# MCU.net
KiCad netlist of a schematic drawn in Altium Designer
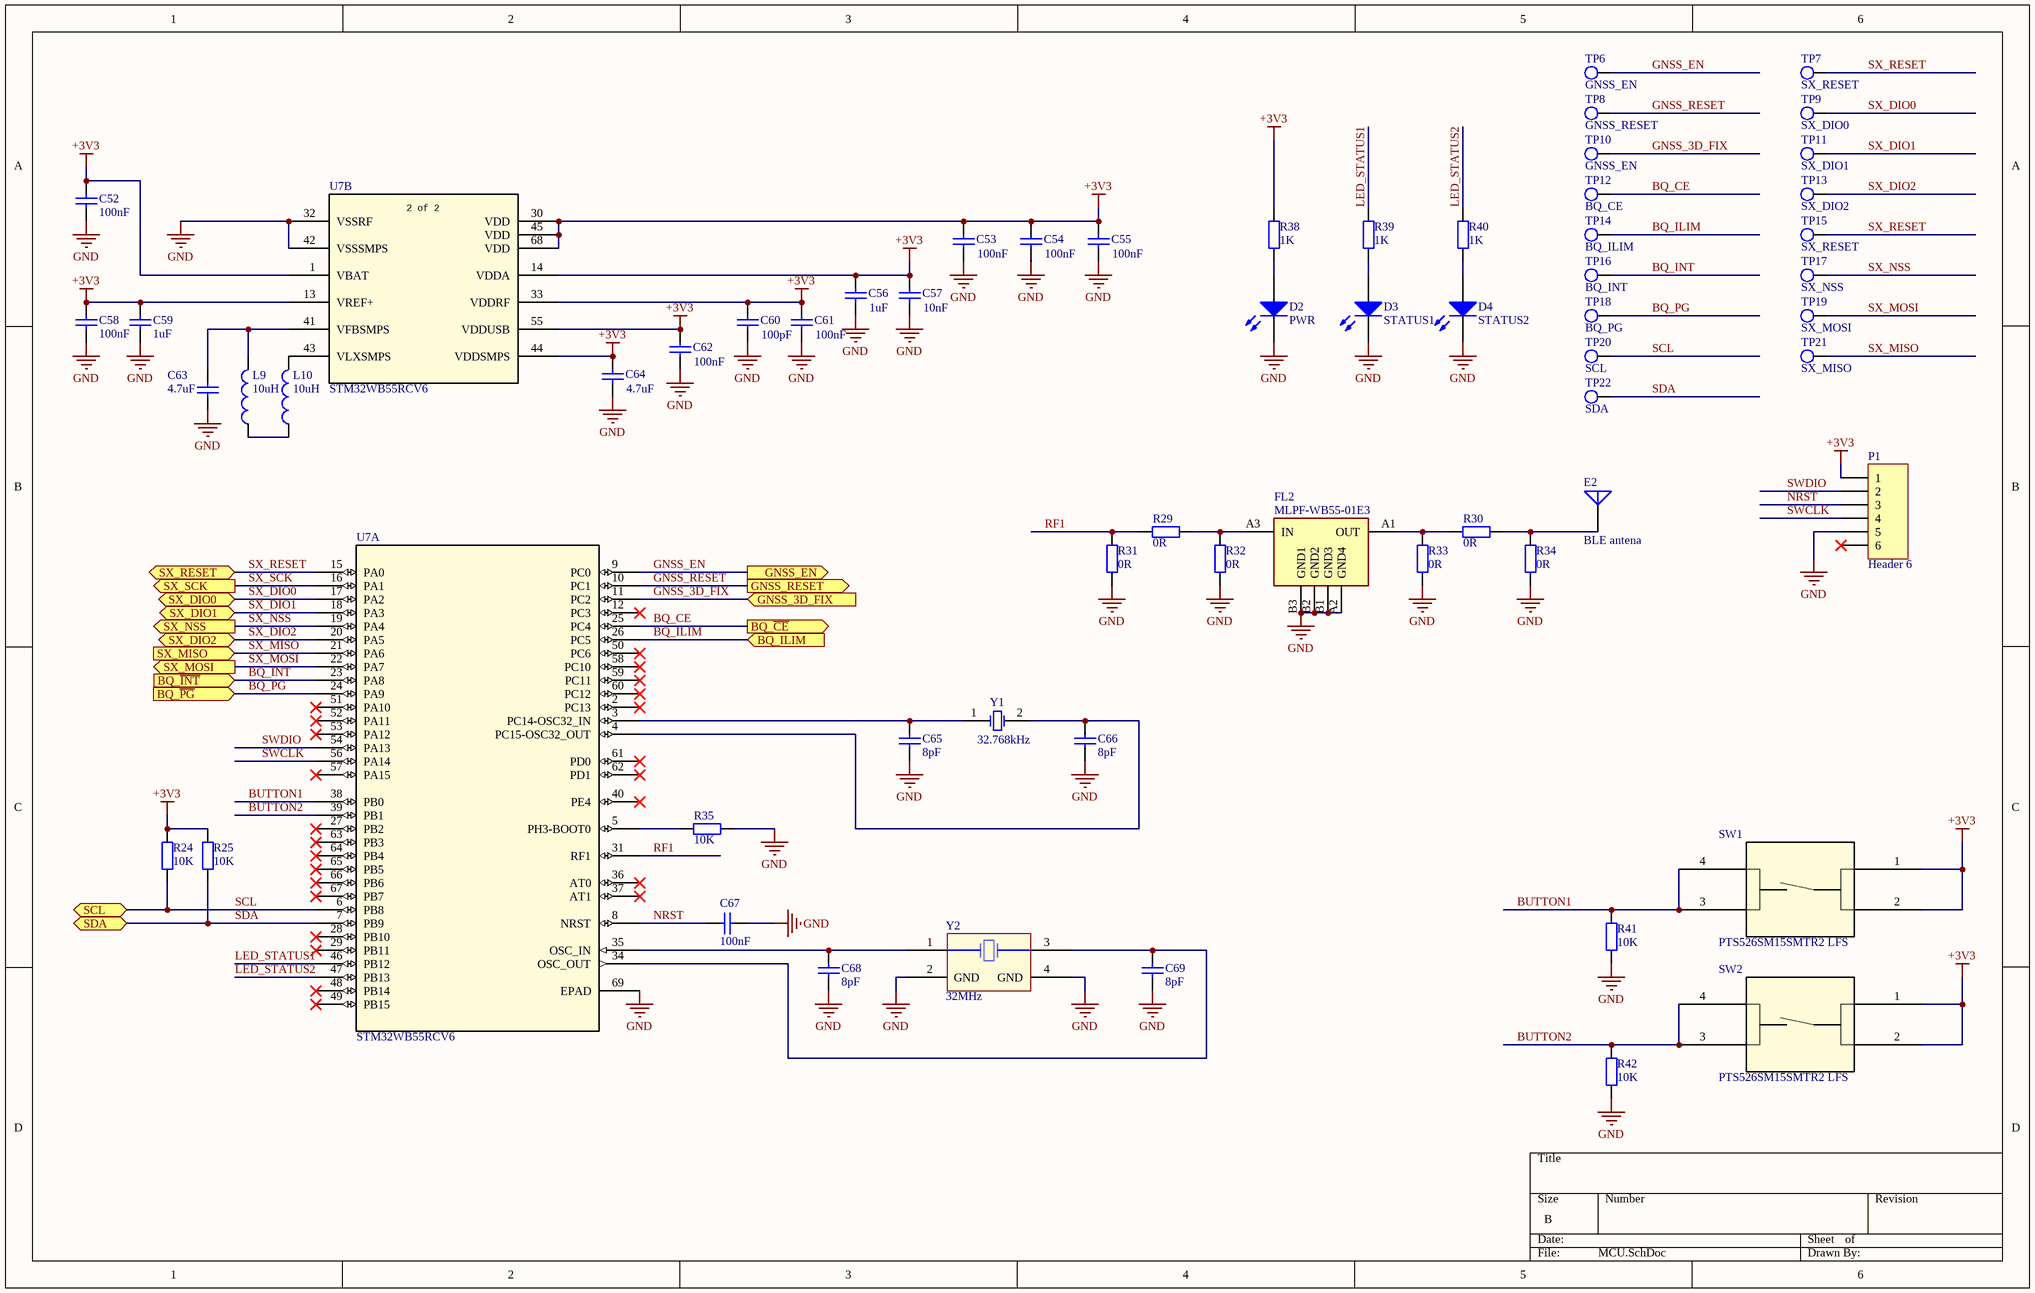
[diagram p0: MCU.SchDoc]

(export (version "E")
  (design (tool "Eeschema 10.0.6"))
  (components
    (comp (ref "C52")
      (value "100nF")
      (footprint "0402")
      (description "Capacitor")
      (fields (field (name "PUBLISHER") "Altium Limited"))
      (libsource (lib "Miscellaneous Devices") (part "Cap"))
    )
    (comp (ref "C53")
      (value "100nF")
      (footprint "0402")
      (description "Capacitor")
      (fields (field (name "PUBLISHER") "Altium Limited"))
      (libsource (lib "Miscellaneous Devices") (part "Cap"))
    )
    (comp (ref "C54")
      (value "100nF")
      (footprint "0402")
      (description "Capacitor")
      (fields (field (name "PUBLISHER") "Altium Limited"))
      (libsource (lib "Miscellaneous Devices") (part "Cap"))
    )
    (comp (ref "C55")
      (value "100nF")
      (footprint "0402")
      (description "Capacitor")
      (fields (field (name "PUBLISHER") "Altium Limited"))
      (libsource (lib "Miscellaneous Devices") (part "Cap"))
    )
    (comp (ref "C56")
      (value "1uF")
      (footprint "0402")
      (description "Capacitor")
      (fields (field (name "PUBLISHER") "Altium Limited"))
      (libsource (lib "Miscellaneous Devices") (part "Cap"))
    )
    (comp (ref "C57")
      (value "10nF")
      (footprint "0402")
      (description "Capacitor")
      (fields (field (name "PUBLISHER") "Altium Limited"))
      (libsource (lib "Miscellaneous Devices") (part "Cap"))
    )
    (comp (ref "C58")
      (value "100nF")
      (footprint "0402")
      (description "Capacitor")
      (fields (field (name "PUBLISHER") "Altium Limited"))
      (libsource (lib "Miscellaneous Devices") (part "Cap"))
    )
    (comp (ref "C59")
      (value "1uF")
      (footprint "0402")
      (description "Capacitor")
      (fields (field (name "PUBLISHER") "Altium Limited"))
      (libsource (lib "Miscellaneous Devices") (part "Cap"))
    )
    (comp (ref "C60")
      (value "100pF")
      (footprint "0402")
      (description "Capacitor")
      (fields (field (name "PUBLISHER") "Altium Limited"))
      (libsource (lib "Miscellaneous Devices") (part "Cap"))
    )
    (comp (ref "C61")
      (value "100nF")
      (footprint "0402")
      (description "Capacitor")
      (fields (field (name "PUBLISHER") "Altium Limited"))
      (libsource (lib "Miscellaneous Devices") (part "Cap"))
    )
    (comp (ref "C62")
      (value "100nF")
      (footprint "0402")
      (description "Capacitor")
      (fields (field (name "PUBLISHER") "Altium Limited"))
      (libsource (lib "Miscellaneous Devices") (part "Cap"))
    )
    (comp (ref "C63")
      (value "4.7uF")
      (footprint "0402")
      (description "Capacitor")
      (fields (field (name "PUBLISHER") "Altium Limited"))
      (libsource (lib "Miscellaneous Devices") (part "Cap"))
    )
    (comp (ref "C64")
      (value "4.7uF")
      (footprint "0402")
      (description "Capacitor")
      (fields (field (name "PUBLISHER") "Altium Limited"))
      (libsource (lib "Miscellaneous Devices") (part "Cap"))
    )
    (comp (ref "C65")
      (value "8pF")
      (footprint "0402")
      (description "Capacitor")
      (fields (field (name "PUBLISHER") "Altium Limited"))
      (libsource (lib "Miscellaneous Devices") (part "Cap"))
    )
    (comp (ref "C66")
      (value "8pF")
      (footprint "0402")
      (description "Capacitor")
      (fields (field (name "PUBLISHER") "Altium Limited"))
      (libsource (lib "Miscellaneous Devices") (part "Cap"))
    )
    (comp (ref "C67")
      (value "100nF")
      (footprint "0402")
      (description "Capacitor")
      (fields (field (name "PUBLISHER") "Altium Limited"))
      (libsource (lib "Miscellaneous Devices") (part "Cap"))
    )
    (comp (ref "C68")
      (value "8pF")
      (footprint "0402")
      (description "Capacitor")
      (fields (field (name "PUBLISHER") "Altium Limited"))
      (libsource (lib "Miscellaneous Devices") (part "Cap"))
    )
    (comp (ref "C69")
      (value "8pF")
      (footprint "0402")
      (description "Capacitor")
      (fields (field (name "PUBLISHER") "Altium Limited"))
      (libsource (lib "Miscellaneous Devices") (part "Cap"))
    )
    (comp (ref "D2")
      (value "PWR")
      (description "SML-D12P8WT86")
      (libsource (lib "Simulation Generic Components") (part "LED"))
    )
    (comp (ref "D3")
      (value "STATUS1")
      (description "SML-D12P8WT86")
      (libsource (lib "Simulation Generic Components") (part "LED"))
    )
    (comp (ref "D4")
      (value "STATUS2")
      (description "SML-D12P8WT86")
      (libsource (lib "Simulation Generic Components") (part "LED"))
    )
    (comp (ref "E2")
      (value "BLE antena")
      (footprint "204286-0001_MOL")
      (description "Generic Antenna")
      (fields (field (name "PUBLISHER") "Altium Limited"))
      (libsource (lib "Miscellaneous Devices") (part "Antenna"))
    )
    (comp (ref "FL2")
      (value "MLPF-WB55-01E3")
      (footprint "MLPF-WB55-01E3")
      (fields (field (name "MOUSER PART NUMBER") "511-MLPF-WB55-01E3"))
      (libsource (lib "Schematic_library") (part "MLPF-WB55-01E3"))
    )
    (comp (ref "L9")
      (value "10uH")
      (footprint "0402-A")
      (description "Inductor")
      (fields (field (name "PUBLISHER") "Altium Limited"))
      (libsource (lib "Miscellaneous Devices") (part "Inductor"))
    )
    (comp (ref "L10")
      (value "10uH")
      (footprint "0402-A")
      (description "Inductor")
      (fields (field (name "PUBLISHER") "Altium Limited"))
      (libsource (lib "Miscellaneous Devices") (part "Inductor"))
    )
    (comp (ref "P1")
      (value "Header 6")
      (footprint "TAG_TC2030-IDC-NL")
      (description "Header, 6-Pin")
      (fields (field (name "PUBLISHER") "Altium Limited"))
      (libsource (lib "Miscellaneous Connectors") (part "Header 6"))
    )
    (comp (ref "R24")
      (value "10K")
      (footprint "SMD-0402-RES")
      (description "Resistor")
      (fields (field (name "PUBLISHER") "Altium Limited"))
      (libsource (lib "Miscellaneous Devices") (part "Res2"))
    )
    (comp (ref "R25")
      (value "10K")
      (footprint "SMD-0402-RES")
      (description "Resistor")
      (fields (field (name "PUBLISHER") "Altium Limited"))
      (libsource (lib "Miscellaneous Devices") (part "Res2"))
    )
    (comp (ref "R29")
      (value "0R")
      (footprint "SMD-0402-RES")
      (description "Resistor")
      (fields (field (name "PUBLISHER") "Altium Limited"))
      (libsource (lib "") (part "Res2_2"))
    )
    (comp (ref "R30")
      (value "0R")
      (footprint "SMD-0402-RES")
      (description "Resistor")
      (fields (field (name "PUBLISHER") "Altium Limited"))
      (libsource (lib "") (part "Res2_2"))
    )
    (comp (ref "R31")
      (value "0R")
      (footprint "SMD-0402-RES")
      (description "Resistor")
      (fields (field (name "PUBLISHER") "Altium Limited"))
      (libsource (lib "Miscellaneous Devices") (part "Res2"))
    )
    (comp (ref "R32")
      (value "0R")
      (footprint "SMD-0402-RES")
      (description "Resistor")
      (fields (field (name "PUBLISHER") "Altium Limited"))
      (libsource (lib "Miscellaneous Devices") (part "Res2"))
    )
    (comp (ref "R33")
      (value "0R")
      (footprint "SMD-0402-RES")
      (description "Resistor")
      (fields (field (name "PUBLISHER") "Altium Limited"))
      (libsource (lib "Miscellaneous Devices") (part "Res2"))
    )
    (comp (ref "R34")
      (value "0R")
      (footprint "SMD-0402-RES")
      (description "Resistor")
      (fields (field (name "PUBLISHER") "Altium Limited"))
      (libsource (lib "Miscellaneous Devices") (part "Res2"))
    )
    (comp (ref "R35")
      (value "10K")
      (footprint "SMD-0402-RES")
      (description "Resistor")
      (fields (field (name "PUBLISHER") "Altium Limited"))
      (libsource (lib "") (part "Res2_3"))
    )
    (comp (ref "R38")
      (value "1K")
      (footprint "SMD-0402-RES")
      (description "Resistor")
      (fields (field (name "PUBLISHER") "Altium Limited"))
      (libsource (lib "") (part "Res2_1"))
    )
    (comp (ref "R39")
      (value "1K")
      (footprint "SMD-0402-RES")
      (description "Resistor")
      (fields (field (name "PUBLISHER") "Altium Limited"))
      (libsource (lib "") (part "Res2_1"))
    )
    (comp (ref "R40")
      (value "1K")
      (footprint "SMD-0402-RES")
      (description "Resistor")
      (fields (field (name "PUBLISHER") "Altium Limited"))
      (libsource (lib "") (part "Res2_1"))
    )
    (comp (ref "R41")
      (value "10K")
      (footprint "SMD-0402-RES")
      (description "Resistor")
      (fields (field (name "PUBLISHER") "Altium Limited"))
      (libsource (lib "") (part "Res2_1"))
    )
    (comp (ref "R42")
      (value "10K")
      (footprint "SMD-0402-RES")
      (description "Resistor")
      (fields (field (name "PUBLISHER") "Altium Limited"))
      (libsource (lib "") (part "Res2_1"))
    )
    (comp (ref "SW1")
      (value "PTS526SM15SMTR2 LFS")
      (footprint "PTS526SM15SMTR2 LFS")
      (fields
        (field (name "MANUFACTURER_PART_NUMBER") "PTS526 SM15 SMTR2 LFS")
        (field (name "COPYRIGHT") "Copyright (C) 2026 Ultra Librarian. All rights reserved.")
      )
      (libsource (lib "Schematic_library") (part "PTS526SM15SMTR2 LFS"))
    )
    (comp (ref "SW2")
      (value "PTS526SM15SMTR2 LFS")
      (footprint "PTS526SM15SMTR2 LFS")
      (fields
        (field (name "MANUFACTURER_PART_NUMBER") "PTS526 SM15 SMTR2 LFS")
        (field (name "COPYRIGHT") "Copyright (C) 2026 Ultra Librarian. All rights reserved.")
      )
      (libsource (lib "Schematic_library") (part "PTS526SM15SMTR2 LFS"))
    )
    (comp (ref "TP6")
      (value "GNSS_EN")
      (footprint "testpoint 1 mm")
      (libsource (lib "Schematic_library") (part "testpoint"))
    )
    (comp (ref "TP7")
      (value "SX_RESET")
      (footprint "testpoint 1 mm")
      (libsource (lib "Schematic_library") (part "testpoint"))
    )
    (comp (ref "TP8")
      (value "GNSS_RESET")
      (footprint "testpoint 1 mm")
      (libsource (lib "Schematic_library") (part "testpoint"))
    )
    (comp (ref "TP9")
      (value "SX_DIO0")
      (footprint "testpoint 1 mm")
      (libsource (lib "Schematic_library") (part "testpoint"))
    )
    (comp (ref "TP10")
      (value "GNSS_EN")
      (footprint "testpoint 1 mm")
      (libsource (lib "Schematic_library") (part "testpoint"))
    )
    (comp (ref "TP11")
      (value "SX_DIO1")
      (footprint "testpoint 1 mm")
      (libsource (lib "Schematic_library") (part "testpoint"))
    )
    (comp (ref "TP12")
      (value "BQ_CE")
      (footprint "testpoint 1 mm")
      (libsource (lib "Schematic_library") (part "testpoint"))
    )
    (comp (ref "TP13")
      (value "SX_DIO2")
      (footprint "testpoint 1 mm")
      (libsource (lib "Schematic_library") (part "testpoint"))
    )
    (comp (ref "TP14")
      (value "BQ_ILIM")
      (footprint "testpoint 1 mm")
      (libsource (lib "Schematic_library") (part "testpoint"))
    )
    (comp (ref "TP15")
      (value "SX_RESET")
      (footprint "testpoint 1 mm")
      (libsource (lib "Schematic_library") (part "testpoint"))
    )
    (comp (ref "TP16")
      (value "BQ_INT")
      (footprint "testpoint 1 mm")
      (libsource (lib "Schematic_library") (part "testpoint"))
    )
    (comp (ref "TP17")
      (value "SX_NSS")
      (footprint "testpoint 1 mm")
      (libsource (lib "Schematic_library") (part "testpoint"))
    )
    (comp (ref "TP18")
      (value "BQ_PG")
      (footprint "testpoint 1 mm")
      (libsource (lib "Schematic_library") (part "testpoint"))
    )
    (comp (ref "TP19")
      (value "SX_MOSI")
      (footprint "testpoint 1 mm")
      (libsource (lib "Schematic_library") (part "testpoint"))
    )
    (comp (ref "TP20")
      (value "SCL")
      (footprint "testpoint 1 mm")
      (libsource (lib "Schematic_library") (part "testpoint"))
    )
    (comp (ref "TP21")
      (value "SX_MISO")
      (footprint "testpoint 1 mm")
      (libsource (lib "Schematic_library") (part "testpoint"))
    )
    (comp (ref "TP22")
      (value "SDA")
      (footprint "testpoint 1 mm")
      (libsource (lib "Schematic_library") (part "testpoint"))
    )
    (comp (ref "U7")
      (value "STM32WB55RCV6")
      (footprint "STM32WB55RCV6")
      (fields (field (name "COPYRIGHT") "Copyright (C) 2025 Ultra Librarian. All rights reserved."))
      (libsource (lib "Schematic_library") (part "STM32WB55RCV6"))
    )
    (comp (ref "Y1")
      (value "32.768kHz")
      (footprint "CM8V-T1A-32.768kHz-7pF-20PPM-TA-QC")
      (description "Crystal Oscillator\r\nCM8V-T1A-32.768kHz-7pF-20PPM-TA-QC")
      (fields (field (name "PUBLISHER") "Altium Limited"))
      (libsource (lib "Miscellaneous Devices") (part "XTAL"))
    )
    (comp (ref "Y2")
      (value "32MHz")
      (footprint "ECS-TXO-20CSMV-320-EY-TR")
      (libsource (lib "Schematic_library") (part "Xtal 4 pin"))
    )
  )
  (nets
    (net (code "1") (name "+3V3") (class "Default")
      (node (ref "C52") (pin "2") (pinfunction "2_2") (pintype "passive"))
      (node (ref "C53") (pin "2") (pinfunction "2_2") (pintype "passive"))
      (node (ref "C54") (pin "2") (pinfunction "2_2") (pintype "passive"))
      (node (ref "C55") (pin "2") (pinfunction "2_2") (pintype "passive"))
      (node (ref "C56") (pin "2") (pinfunction "2_2") (pintype "passive"))
      (node (ref "C57") (pin "2") (pinfunction "2_2") (pintype "passive"))
      (node (ref "C58") (pin "2") (pinfunction "2_2") (pintype "passive"))
      (node (ref "C59") (pin "2") (pinfunction "2_2") (pintype "passive"))
      (node (ref "C60") (pin "2") (pinfunction "2_2") (pintype "passive"))
      (node (ref "C61") (pin "2") (pinfunction "2_2") (pintype "passive"))
      (node (ref "C62") (pin "2") (pinfunction "2_2") (pintype "passive"))
      (node (ref "C64") (pin "2") (pinfunction "2_2") (pintype "passive"))
      (node (ref "P1") (pin "1") (pinfunction "1_1") (pintype "passive"))
      (node (ref "R24") (pin "2") (pinfunction "2_2") (pintype "passive"))
      (node (ref "R25") (pin "2") (pinfunction "2_2") (pintype "passive"))
      (node (ref "R38") (pin "1") (pinfunction "1_1") (pintype "passive"))
      (node (ref "SW1") (pin "1") (pinfunction "1_1") (pintype "passive"))
      (node (ref "SW1") (pin "2") (pinfunction "2_2") (pintype "passive"))
      (node (ref "SW2") (pin "1") (pinfunction "1_1") (pintype "passive"))
      (node (ref "SW2") (pin "2") (pinfunction "2_2") (pintype "passive"))
      (node (ref "U7") (pin "1") (pinfunction "VBAT_1") (pintype "power_in"))
      (node (ref "U7") (pin "13") (pinfunction "VREF+_13") (pintype "power_in"))
      (node (ref "U7") (pin "14") (pinfunction "VDDA_14") (pintype "power_in"))
      (node (ref "U7") (pin "30") (pinfunction "VDD_30") (pintype "power_in"))
      (node (ref "U7") (pin "33") (pinfunction "VDDRF_33") (pintype "power_in"))
      (node (ref "U7") (pin "44") (pinfunction "VDDSMPS_44") (pintype "power_in"))
      (node (ref "U7") (pin "45") (pinfunction "VDD_45") (pintype "power_in"))
      (node (ref "U7") (pin "55") (pinfunction "VDDUSB_55") (pintype "power_in"))
      (node (ref "U7") (pin "68") (pinfunction "VDD_68") (pintype "power_in"))
    )
    (net (code "2") (name "/BQ_CE") (class "Default")
      (node (ref "TP12") (pin "1") (pinfunction "1_1") (pintype "passive"))
      (node (ref "U7") (pin "25") (pinfunction "PC4_25") (pintype "bidirectional"))
    )
    (net (code "3") (name "/BQ_ILIM") (class "Default")
      (node (ref "TP14") (pin "1") (pinfunction "1_1") (pintype "passive"))
      (node (ref "U7") (pin "26") (pinfunction "PC5_26") (pintype "bidirectional"))
    )
    (net (code "4") (name "/BQ_INT") (class "Default")
      (node (ref "TP16") (pin "1") (pinfunction "1_1") (pintype "passive"))
      (node (ref "U7") (pin "23") (pinfunction "PA8_23") (pintype "bidirectional"))
    )
    (net (code "5") (name "/BQ_PG") (class "Default")
      (node (ref "TP18") (pin "1") (pinfunction "1_1") (pintype "passive"))
      (node (ref "U7") (pin "24") (pinfunction "PA9_24") (pintype "bidirectional"))
    )
    (net (code "6") (name "/BUTTON1") (class "Default")
      (node (ref "R41") (pin "1") (pinfunction "1_1") (pintype "passive"))
      (node (ref "SW1") (pin "3") (pinfunction "3_3") (pintype "passive"))
      (node (ref "SW1") (pin "4") (pinfunction "4_4") (pintype "passive"))
      (node (ref "U7") (pin "38") (pinfunction "PB0_38") (pintype "bidirectional"))
    )
    (net (code "7") (name "/BUTTON2") (class "Default")
      (node (ref "R42") (pin "1") (pinfunction "1_1") (pintype "passive"))
      (node (ref "SW2") (pin "3") (pinfunction "3_3") (pintype "passive"))
      (node (ref "SW2") (pin "4") (pinfunction "4_4") (pintype "passive"))
      (node (ref "U7") (pin "39") (pinfunction "PB1_39") (pintype "bidirectional"))
    )
    (net (code "8") (name "/GNSS_3D_FIX") (class "Default")
      (node (ref "TP10") (pin "1") (pinfunction "1_1") (pintype "passive"))
      (node (ref "U7") (pin "11") (pinfunction "PC2_11") (pintype "bidirectional"))
    )
    (net (code "9") (name "/GNSS_EN") (class "Default")
      (node (ref "TP6") (pin "1") (pinfunction "1_1") (pintype "passive"))
      (node (ref "U7") (pin "9") (pinfunction "PC0_9") (pintype "bidirectional"))
    )
    (net (code "10") (name "/GNSS_RESET") (class "Default")
      (node (ref "TP8") (pin "1") (pinfunction "1_1") (pintype "passive"))
      (node (ref "U7") (pin "10") (pinfunction "PC1_10") (pintype "bidirectional"))
    )
    (net (code "11") (name "/LED_STATUS1") (class "Default")
      (node (ref "R39") (pin "1") (pinfunction "1_1") (pintype "passive"))
      (node (ref "U7") (pin "46") (pinfunction "PB12_46") (pintype "bidirectional"))
    )
    (net (code "12") (name "/LED_STATUS2") (class "Default")
      (node (ref "R40") (pin "1") (pinfunction "1_1") (pintype "passive"))
      (node (ref "U7") (pin "47") (pinfunction "PB13_47") (pintype "bidirectional"))
    )
    (net (code "13") (name "/NRST") (class "Default")
      (node (ref "C67") (pin "2") (pinfunction "2_2") (pintype "passive"))
      (node (ref "P1") (pin "3") (pinfunction "3_3") (pintype "passive"))
      (node (ref "U7") (pin "8") (pinfunction "NRST_8") (pintype "bidirectional"))
    )
    (net (code "14") (name "/RF1") (class "Default")
      (node (ref "R29") (pin "2") (pinfunction "2_2") (pintype "passive"))
      (node (ref "R31") (pin "2") (pinfunction "2_2") (pintype "passive"))
      (node (ref "U7") (pin "31") (pinfunction "RF1_31") (pintype "bidirectional"))
    )
    (net (code "15") (name "/SCL") (class "Default")
      (node (ref "R24") (pin "1") (pinfunction "1_1") (pintype "passive"))
      (node (ref "TP20") (pin "1") (pinfunction "1_1") (pintype "passive"))
      (node (ref "U7") (pin "6") (pinfunction "PB8_6") (pintype "bidirectional"))
    )
    (net (code "16") (name "/SDA") (class "Default")
      (node (ref "R25") (pin "1") (pinfunction "1_1") (pintype "passive"))
      (node (ref "TP22") (pin "1") (pinfunction "1_1") (pintype "passive"))
      (node (ref "U7") (pin "7") (pinfunction "PB9_7") (pintype "bidirectional"))
    )
    (net (code "17") (name "/SWCLK") (class "Default")
      (node (ref "P1") (pin "4") (pinfunction "4_4") (pintype "passive"))
      (node (ref "U7") (pin "56") (pinfunction "PA14_56") (pintype "bidirectional"))
    )
    (net (code "18") (name "/SWDIO") (class "Default")
      (node (ref "P1") (pin "2") (pinfunction "2_2") (pintype "passive"))
      (node (ref "U7") (pin "54") (pinfunction "PA13_54") (pintype "bidirectional"))
    )
    (net (code "19") (name "/SX_DIO0") (class "Default")
      (node (ref "TP9") (pin "1") (pinfunction "1_1") (pintype "passive"))
      (node (ref "U7") (pin "17") (pinfunction "PA2_17") (pintype "bidirectional"))
    )
    (net (code "20") (name "/SX_DIO1") (class "Default")
      (node (ref "TP11") (pin "1") (pinfunction "1_1") (pintype "passive"))
      (node (ref "U7") (pin "18") (pinfunction "PA3_18") (pintype "bidirectional"))
    )
    (net (code "21") (name "/SX_DIO2") (class "Default")
      (node (ref "TP13") (pin "1") (pinfunction "1_1") (pintype "passive"))
      (node (ref "U7") (pin "20") (pinfunction "PA5_20") (pintype "bidirectional"))
    )
    (net (code "22") (name "/SX_MISO") (class "Default")
      (node (ref "TP21") (pin "1") (pinfunction "1_1") (pintype "passive"))
      (node (ref "U7") (pin "21") (pinfunction "PA6_21") (pintype "bidirectional"))
    )
    (net (code "23") (name "/SX_MOSI") (class "Default")
      (node (ref "TP19") (pin "1") (pinfunction "1_1") (pintype "passive"))
      (node (ref "U7") (pin "22") (pinfunction "PA7_22") (pintype "bidirectional"))
    )
    (net (code "24") (name "/SX_NSS") (class "Default")
      (node (ref "TP17") (pin "1") (pinfunction "1_1") (pintype "passive"))
      (node (ref "U7") (pin "19") (pinfunction "PA4_19") (pintype "bidirectional"))
    )
    (net (code "25") (name "/SX_RESET") (class "Default")
      (node (ref "TP15") (pin "1") (pinfunction "1_1") (pintype "passive"))
      (node (ref "TP7") (pin "1") (pinfunction "1_1") (pintype "passive"))
      (node (ref "U7") (pin "15") (pinfunction "PA0_15") (pintype "bidirectional"))
    )
    (net (code "26") (name "/SX_SCK") (class "Default")
      (node (ref "U7") (pin "16") (pinfunction "PA1_16") (pintype "bidirectional"))
    )
    (net (code "27") (name "GND") (class "Default")
      (node (ref "C52") (pin "1") (pinfunction "1_1") (pintype "passive"))
      (node (ref "C53") (pin "1") (pinfunction "1_1") (pintype "passive"))
      (node (ref "C54") (pin "1") (pinfunction "1_1") (pintype "passive"))
      (node (ref "C55") (pin "1") (pinfunction "1_1") (pintype "passive"))
      (node (ref "C56") (pin "1") (pinfunction "1_1") (pintype "passive"))
      (node (ref "C57") (pin "1") (pinfunction "1_1") (pintype "passive"))
      (node (ref "C58") (pin "1") (pinfunction "1_1") (pintype "passive"))
      (node (ref "C59") (pin "1") (pinfunction "1_1") (pintype "passive"))
      (node (ref "C60") (pin "1") (pinfunction "1_1") (pintype "passive"))
      (node (ref "C61") (pin "1") (pinfunction "1_1") (pintype "passive"))
      (node (ref "C62") (pin "1") (pinfunction "1_1") (pintype "passive"))
      (node (ref "C63") (pin "1") (pinfunction "1_1") (pintype "passive"))
      (node (ref "C64") (pin "1") (pinfunction "1_1") (pintype "passive"))
      (node (ref "C65") (pin "2") (pinfunction "2_2") (pintype "passive"))
      (node (ref "C66") (pin "2") (pinfunction "2_2") (pintype "passive"))
      (node (ref "C67") (pin "1") (pinfunction "1_1") (pintype "passive"))
      (node (ref "C68") (pin "2") (pinfunction "2_2") (pintype "passive"))
      (node (ref "C69") (pin "2") (pinfunction "2_2") (pintype "passive"))
      (node (ref "D2") (pin "2") (pinfunction "K_2") (pintype "passive"))
      (node (ref "D3") (pin "2") (pinfunction "K_2") (pintype "passive"))
      (node (ref "D4") (pin "2") (pinfunction "K_2") (pintype "passive"))
      (node (ref "FL2") (pin "A2") (pinfunction "GND4_A2") (pintype "passive"))
      (node (ref "FL2") (pin "B1") (pinfunction "GND3_B1") (pintype "passive"))
      (node (ref "FL2") (pin "B2") (pinfunction "GND2_B2") (pintype "passive"))
      (node (ref "FL2") (pin "B3") (pinfunction "GND1_B3") (pintype "passive"))
      (node (ref "P1") (pin "5") (pinfunction "5_5") (pintype "passive"))
      (node (ref "R31") (pin "1") (pinfunction "1_1") (pintype "passive"))
      (node (ref "R32") (pin "1") (pinfunction "1_1") (pintype "passive"))
      (node (ref "R33") (pin "1") (pinfunction "1_1") (pintype "passive"))
      (node (ref "R34") (pin "1") (pinfunction "1_1") (pintype "passive"))
      (node (ref "R35") (pin "2") (pinfunction "2_2") (pintype "passive"))
      (node (ref "R41") (pin "2") (pinfunction "2_2") (pintype "passive"))
      (node (ref "R42") (pin "2") (pinfunction "2_2") (pintype "passive"))
      (node (ref "U7") (pin "32") (pinfunction "VSSRF_32") (pintype "power_in"))
      (node (ref "U7") (pin "42") (pinfunction "VSSSMPS_42") (pintype "power_in"))
      (node (ref "U7") (pin "69") (pinfunction "EPAD_69") (pintype "passive"))
      (node (ref "Y2") (pin "2") (pinfunction "GND_2") (pintype "passive"))
      (node (ref "Y2") (pin "4") (pinfunction "GND_4") (pintype "passive"))
    )
    (net (code "28") (name "Net-(D2-A)") (class "Default")
      (node (ref "D2") (pin "1") (pinfunction "A_1") (pintype "passive"))
      (node (ref "R38") (pin "2") (pinfunction "2_2") (pintype "passive"))
    )
    (net (code "29") (name "Net-(D3-A)") (class "Default")
      (node (ref "D3") (pin "1") (pinfunction "A_1") (pintype "passive"))
      (node (ref "R39") (pin "2") (pinfunction "2_2") (pintype "passive"))
    )
    (net (code "30") (name "Net-(D4-A)") (class "Default")
      (node (ref "D4") (pin "1") (pinfunction "A_1") (pintype "passive"))
      (node (ref "R40") (pin "2") (pinfunction "2_2") (pintype "passive"))
    )
    (net (code "31") (name "Net-(E2-A)") (class "Default")
      (node (ref "E2") (pin "1") (pinfunction "A_1") (pintype "passive"))
      (node (ref "R30") (pin "1") (pinfunction "1_1") (pintype "passive"))
      (node (ref "R34") (pin "2") (pinfunction "2_2") (pintype "passive"))
    )
    (net (code "32") (name "Net-(FL2-IN)") (class "Default")
      (node (ref "FL2") (pin "A3") (pinfunction "IN_A3") (pintype "passive"))
      (node (ref "R29") (pin "1") (pinfunction "1_1") (pintype "passive"))
      (node (ref "R32") (pin "2") (pinfunction "2_2") (pintype "passive"))
    )
    (net (code "33") (name "Net-(FL2-OUT)") (class "Default")
      (node (ref "FL2") (pin "A1") (pinfunction "OUT_A1") (pintype "passive"))
      (node (ref "R30") (pin "2") (pinfunction "2_2") (pintype "passive"))
      (node (ref "R33") (pin "2") (pinfunction "2_2") (pintype "passive"))
    )
    (net (code "34") (name "Net-(L10-Pad1)") (class "Default")
      (node (ref "L10") (pin "1") (pinfunction "1_1") (pintype "passive"))
      (node (ref "L9") (pin "1") (pinfunction "1_1") (pintype "passive"))
    )
    (net (code "35") (name "Net-(U7A-OSC_IN)") (class "Default")
      (node (ref "C68") (pin "1") (pinfunction "1_1") (pintype "passive"))
      (node (ref "U7") (pin "35") (pinfunction "OSC_IN_35") (pintype "input"))
      (node (ref "Y2") (pin "1") (pinfunction "1_1") (pintype "passive"))
    )
    (net (code "36") (name "Net-(U7A-OSC_OUT)") (class "Default")
      (node (ref "C69") (pin "1") (pinfunction "1_1") (pintype "passive"))
      (node (ref "U7") (pin "34") (pinfunction "OSC_OUT_34") (pintype "output"))
      (node (ref "Y2") (pin "3") (pinfunction "3_3") (pintype "passive"))
    )
    (net (code "37") (name "Net-(U7A-PC14-OSC32_IN)") (class "Default")
      (node (ref "C65") (pin "1") (pinfunction "1_1") (pintype "passive"))
      (node (ref "U7") (pin "3") (pinfunction "PC14-OSC32_IN_3") (pintype "bidirectional"))
      (node (ref "Y1") (pin "1") (pinfunction "OSC1_1") (pintype "passive"))
    )
    (net (code "38") (name "Net-(U7A-PC15-OSC32_OUT)") (class "Default")
      (node (ref "C66") (pin "1") (pinfunction "1_1") (pintype "passive"))
      (node (ref "U7") (pin "4") (pinfunction "PC15-OSC32_OUT_4") (pintype "bidirectional"))
      (node (ref "Y1") (pin "2") (pinfunction "OSC2_2") (pintype "passive"))
    )
    (net (code "39") (name "Net-(U7A-PH3-BOOT0)") (class "Default")
      (node (ref "R35") (pin "1") (pinfunction "1_1") (pintype "passive"))
      (node (ref "U7") (pin "5") (pinfunction "PH3-BOOT0_5") (pintype "bidirectional"))
    )
    (net (code "40") (name "Net-(U7B-VFBSMPS)") (class "Default")
      (node (ref "C63") (pin "2") (pinfunction "2_2") (pintype "passive"))
      (node (ref "L9") (pin "2") (pinfunction "2_2") (pintype "passive"))
      (node (ref "U7") (pin "41") (pinfunction "VFBSMPS_41") (pintype "power_in"))
    )
    (net (code "41") (name "Net-(U7B-VLXSMPS)") (class "Default")
      (node (ref "L10") (pin "2") (pinfunction "2_2") (pintype "passive"))
      (node (ref "U7") (pin "43") (pinfunction "VLXSMPS_43") (pintype "power_in"))
    )
    (net (code "42") (name "unconnected-(P1-Pad6)") (class "Default")
      (node (ref "P1") (pin "6") (pinfunction "6_6") (pintype "passive+no_connect"))
    )
    (net (code "43") (name "unconnected-(U7A-AT0-Pad36)") (class "Default")
      (node (ref "U7") (pin "36") (pinfunction "AT0_36") (pintype "bidirectional+no_connect"))
    )
    (net (code "44") (name "unconnected-(U7A-AT1-Pad37)") (class "Default")
      (node (ref "U7") (pin "37") (pinfunction "AT1_37") (pintype "bidirectional+no_connect"))
    )
    (net (code "45") (name "unconnected-(U7A-PA10-Pad51)") (class "Default")
      (node (ref "U7") (pin "51") (pinfunction "PA10_51") (pintype "bidirectional+no_connect"))
    )
    (net (code "46") (name "unconnected-(U7A-PA11-Pad52)") (class "Default")
      (node (ref "U7") (pin "52") (pinfunction "PA11_52") (pintype "bidirectional+no_connect"))
    )
    (net (code "47") (name "unconnected-(U7A-PA12-Pad53)") (class "Default")
      (node (ref "U7") (pin "53") (pinfunction "PA12_53") (pintype "bidirectional+no_connect"))
    )
    (net (code "48") (name "unconnected-(U7A-PA15-Pad57)") (class "Default")
      (node (ref "U7") (pin "57") (pinfunction "PA15_57") (pintype "bidirectional+no_connect"))
    )
    (net (code "49") (name "unconnected-(U7A-PB2-Pad27)") (class "Default")
      (node (ref "U7") (pin "27") (pinfunction "PB2_27") (pintype "bidirectional+no_connect"))
    )
    (net (code "50") (name "unconnected-(U7A-PB3-Pad63)") (class "Default")
      (node (ref "U7") (pin "63") (pinfunction "PB3_63") (pintype "bidirectional+no_connect"))
    )
    (net (code "51") (name "unconnected-(U7A-PB4-Pad64)") (class "Default")
      (node (ref "U7") (pin "64") (pinfunction "PB4_64") (pintype "bidirectional+no_connect"))
    )
    (net (code "52") (name "unconnected-(U7A-PB5-Pad65)") (class "Default")
      (node (ref "U7") (pin "65") (pinfunction "PB5_65") (pintype "bidirectional+no_connect"))
    )
    (net (code "53") (name "unconnected-(U7A-PB6-Pad66)") (class "Default")
      (node (ref "U7") (pin "66") (pinfunction "PB6_66") (pintype "bidirectional+no_connect"))
    )
    (net (code "54") (name "unconnected-(U7A-PB7-Pad67)") (class "Default")
      (node (ref "U7") (pin "67") (pinfunction "PB7_67") (pintype "bidirectional+no_connect"))
    )
    (net (code "55") (name "unconnected-(U7A-PB10-Pad28)") (class "Default")
      (node (ref "U7") (pin "28") (pinfunction "PB10_28") (pintype "bidirectional+no_connect"))
    )
    (net (code "56") (name "unconnected-(U7A-PB11-Pad29)") (class "Default")
      (node (ref "U7") (pin "29") (pinfunction "PB11_29") (pintype "bidirectional+no_connect"))
    )
    (net (code "57") (name "unconnected-(U7A-PB14-Pad48)") (class "Default")
      (node (ref "U7") (pin "48") (pinfunction "PB14_48") (pintype "bidirectional+no_connect"))
    )
    (net (code "58") (name "unconnected-(U7A-PB15-Pad49)") (class "Default")
      (node (ref "U7") (pin "49") (pinfunction "PB15_49") (pintype "bidirectional+no_connect"))
    )
    (net (code "59") (name "unconnected-(U7A-PC3-Pad12)") (class "Default")
      (node (ref "U7") (pin "12") (pinfunction "PC3_12") (pintype "bidirectional+no_connect"))
    )
    (net (code "60") (name "unconnected-(U7A-PC6-Pad50)") (class "Default")
      (node (ref "U7") (pin "50") (pinfunction "PC6_50") (pintype "bidirectional+no_connect"))
    )
    (net (code "61") (name "unconnected-(U7A-PC10-Pad58)") (class "Default")
      (node (ref "U7") (pin "58") (pinfunction "PC10_58") (pintype "bidirectional+no_connect"))
    )
    (net (code "62") (name "unconnected-(U7A-PC11-Pad59)") (class "Default")
      (node (ref "U7") (pin "59") (pinfunction "PC11_59") (pintype "bidirectional+no_connect"))
    )
    (net (code "63") (name "unconnected-(U7A-PC12-Pad60)") (class "Default")
      (node (ref "U7") (pin "60") (pinfunction "PC12_60") (pintype "bidirectional+no_connect"))
    )
    (net (code "64") (name "unconnected-(U7A-PC13-Pad2)") (class "Default")
      (node (ref "U7") (pin "2") (pinfunction "PC13_2") (pintype "bidirectional+no_connect"))
    )
    (net (code "65") (name "unconnected-(U7A-PD0-Pad61)") (class "Default")
      (node (ref "U7") (pin "61") (pinfunction "PD0_61") (pintype "bidirectional+no_connect"))
    )
    (net (code "66") (name "unconnected-(U7A-PD1-Pad62)") (class "Default")
      (node (ref "U7") (pin "62") (pinfunction "PD1_62") (pintype "bidirectional+no_connect"))
    )
    (net (code "67") (name "unconnected-(U7A-PE4-Pad40)") (class "Default")
      (node (ref "U7") (pin "40") (pinfunction "PE4_40") (pintype "bidirectional+no_connect"))
    )
  )
)
